# HuckyV2.net
KiCad netlist of a schematic drawn in EAGLE
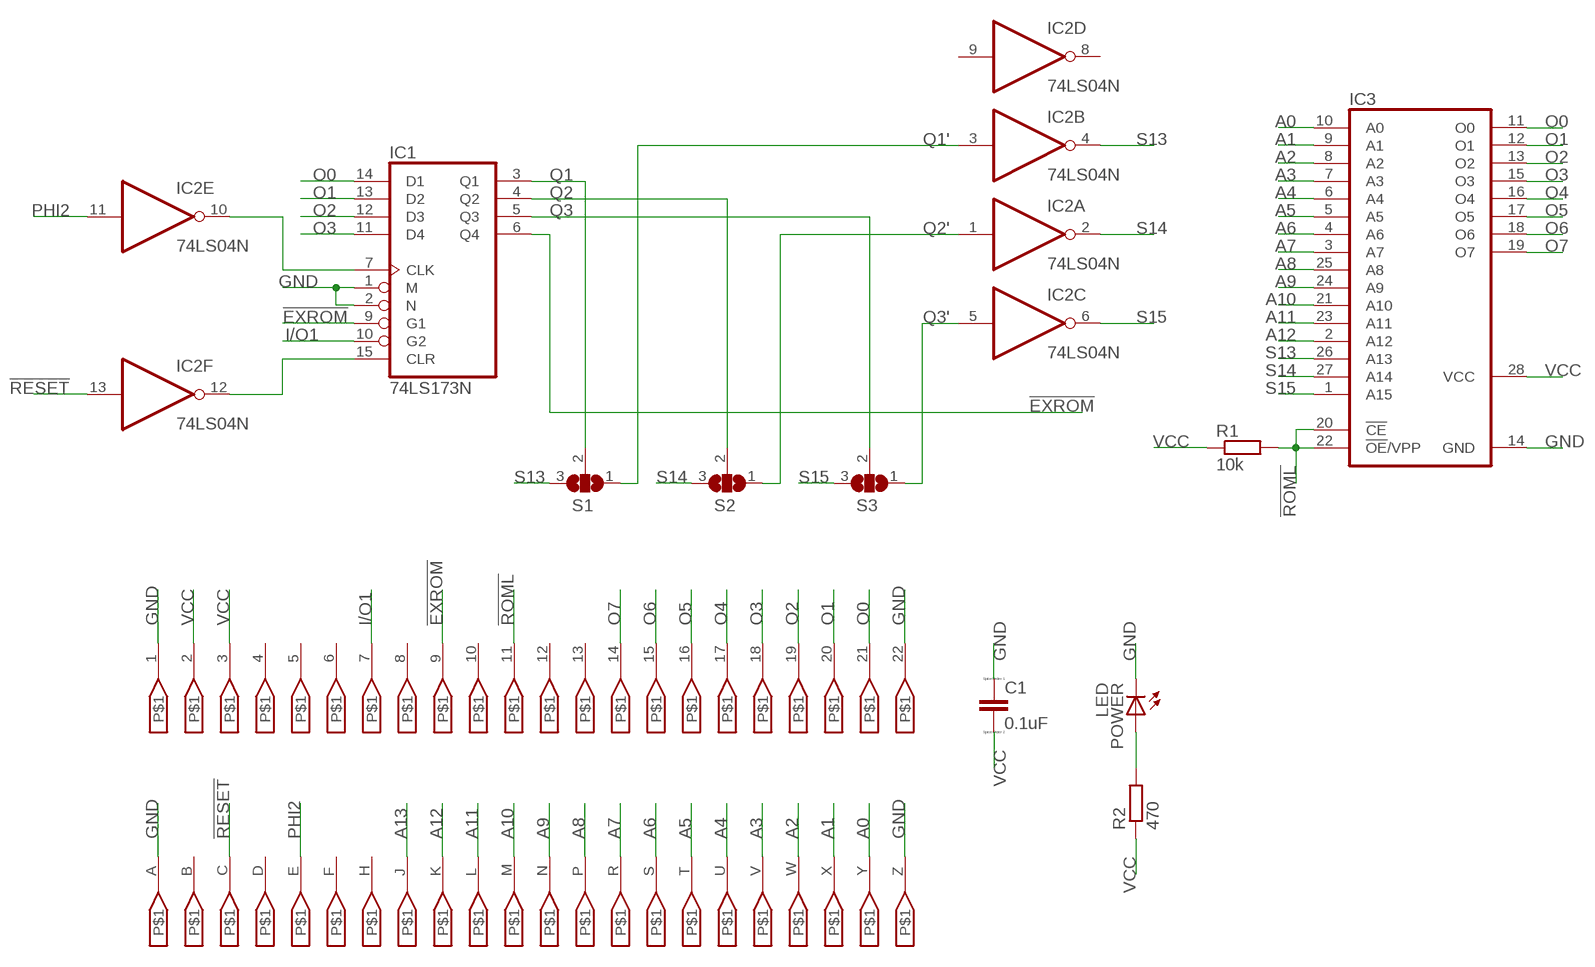
[diagram p0: schematic, sheet 1]

(export (version "E")
  (design (tool "Eeschema 10.0.6"))
  (components
    (comp (ref "C1")
      (value "0.1uF")
      (footprint "eagle-import:C050-24X044_SP")
      (libsource (lib "eagle-import") (part "C-EU050-24X044_SP"))
    )
    (comp (ref "IC1")
      (value "74LS173N")
      (footprint "eagle-import:DIL16")
      (libsource (lib "eagle-import") (part "74173NLS"))
    )
    (comp (ref "IC2")
      (value "74LS04N")
      (footprint "eagle-import:DIL14")
      (libsource (lib "eagle-import") (part "7404NLS"))
    )
    (comp (ref "IC3")
      (value "27C512D")
      (footprint "eagle-import:DIL28-6")
      (fields (field (name "MPN") "M27C512-10F1"))
      (libsource (lib "eagle-import") (part "27C512D"))
    )
    (comp (ref "POWER")
      (value "LED")
      (footprint "eagle-import:LED3MM_SMALLER_DRILL")
      (libsource (lib "eagle-import") (part "TLLG4400_SD"))
    )
    (comp (ref "R1")
      (value "10k")
      (footprint "eagle-import:0207_10_SP")
      (libsource (lib "eagle-import") (part "R-EU_0207/10_SP"))
    )
    (comp (ref "R2")
      (value "470")
      (footprint "eagle-import:0207_10_SP")
      (libsource (lib "eagle-import") (part "R-EU_0207/10_SP"))
    )
    (comp (ref "S1")
      (value "SJ2W_NUMBERED")
      (footprint "eagle-import:SJ_2_NUM")
      (libsource (lib "eagle-import") (part "SJ2W_NUMBERED"))
    )
    (comp (ref "S2")
      (value "SJ2W_NUMBERED")
      (footprint "eagle-import:SJ_2_NUM")
      (libsource (lib "eagle-import") (part "SJ2W_NUMBERED"))
    )
    (comp (ref "S3")
      (value "SJ2W_NUMBERED")
      (footprint "eagle-import:SJ_2_NUM")
      (libsource (lib "eagle-import") (part "SJ2W_NUMBERED"))
    )
    (comp (ref "U$1")
      (value "C64_EXPANSION_FINGERS_PIN8X1.9")
      (footprint "eagle-import:C64_EXPANSION_FINGERS_THINNER")
      (libsource (lib "eagle-import") (part "C64_EXPANSION_FINGERS_PIN8X1.9"))
    )
  )
  (nets
    (net (code "1") (name "/A0") (class "Default")
      (node (ref "IC3") (pin "10") (pinfunction "A0_10") (pintype "input"))
      (node (ref "U$1") (pin "Y") (pinfunction "P$1_Y") (pintype "bidirectional"))
    )
    (net (code "2") (name "/A1") (class "Default")
      (node (ref "IC3") (pin "9") (pinfunction "A1_9") (pintype "input"))
      (node (ref "U$1") (pin "X") (pinfunction "P$1_X") (pintype "bidirectional"))
    )
    (net (code "3") (name "/A2") (class "Default")
      (node (ref "IC3") (pin "8") (pinfunction "A2_8") (pintype "input"))
      (node (ref "U$1") (pin "W") (pinfunction "P$1_W") (pintype "bidirectional"))
    )
    (net (code "4") (name "/A3") (class "Default")
      (node (ref "IC3") (pin "7") (pinfunction "A3_7") (pintype "input"))
      (node (ref "U$1") (pin "V") (pinfunction "P$1_V") (pintype "bidirectional"))
    )
    (net (code "5") (name "/A4") (class "Default")
      (node (ref "IC3") (pin "6") (pinfunction "A4_6") (pintype "input"))
      (node (ref "U$1") (pin "U") (pinfunction "P$1_U") (pintype "bidirectional"))
    )
    (net (code "6") (name "/A5") (class "Default")
      (node (ref "IC3") (pin "5") (pinfunction "A5_5") (pintype "input"))
      (node (ref "U$1") (pin "T") (pinfunction "P$1_T") (pintype "bidirectional"))
    )
    (net (code "7") (name "/A6") (class "Default")
      (node (ref "IC3") (pin "4") (pinfunction "A6_4") (pintype "input"))
      (node (ref "U$1") (pin "S") (pinfunction "P$1_S") (pintype "bidirectional"))
    )
    (net (code "8") (name "/A7") (class "Default")
      (node (ref "IC3") (pin "3") (pinfunction "A7_3") (pintype "input"))
      (node (ref "U$1") (pin "R") (pinfunction "P$1_R") (pintype "bidirectional"))
    )
    (net (code "9") (name "/A8") (class "Default")
      (node (ref "IC3") (pin "25") (pinfunction "A8_25") (pintype "input"))
      (node (ref "U$1") (pin "P") (pinfunction "P$1_P") (pintype "bidirectional"))
    )
    (net (code "10") (name "/A9") (class "Default")
      (node (ref "IC3") (pin "24") (pinfunction "A9_24") (pintype "input"))
      (node (ref "U$1") (pin "N") (pinfunction "P$1_N") (pintype "bidirectional"))
    )
    (net (code "11") (name "/A10") (class "Default")
      (node (ref "IC3") (pin "21") (pinfunction "A10_21") (pintype "input"))
      (node (ref "U$1") (pin "M") (pinfunction "P$1_M") (pintype "bidirectional"))
    )
    (net (code "12") (name "/A11") (class "Default")
      (node (ref "IC3") (pin "23") (pinfunction "A11_23") (pintype "input"))
      (node (ref "U$1") (pin "L") (pinfunction "P$1_L") (pintype "bidirectional"))
    )
    (net (code "13") (name "/A12") (class "Default")
      (node (ref "IC3") (pin "2") (pinfunction "A12_2") (pintype "input"))
      (node (ref "U$1") (pin "K") (pinfunction "P$1_K") (pintype "bidirectional"))
    )
    (net (code "14") (name "/A13") (class "Default")
      (node (ref "U$1") (pin "J") (pinfunction "P$1_J") (pintype "bidirectional"))
    )
    (net (code "15") (name "/GND") (class "Default")
      (node (ref "C1") (pin "1") (pinfunction "1_1") (pintype "passive"))
      (node (ref "IC1") (pin "1") (pinfunction "M_1") (pintype "input"))
      (node (ref "IC1") (pin "2") (pinfunction "N_2") (pintype "input"))
      (node (ref "IC3") (pin "14") (pinfunction "GND_14") (pintype "power_in"))
      (node (ref "POWER") (pin "K") (pinfunction "C_K") (pintype "passive"))
      (node (ref "U$1") (pin "1") (pinfunction "P$1_1") (pintype "bidirectional"))
      (node (ref "U$1") (pin "22") (pinfunction "P$1_22") (pintype "bidirectional"))
      (node (ref "U$1") (pin "A") (pinfunction "P$1_A") (pintype "bidirectional"))
      (node (ref "U$1") (pin "Z") (pinfunction "P$1_Z") (pintype "bidirectional"))
    )
    (net (code "16") (name "/I{slash}O1") (class "Default")
      (node (ref "IC1") (pin "10") (pinfunction "G2_10") (pintype "input"))
      (node (ref "U$1") (pin "7") (pinfunction "P$1_7") (pintype "bidirectional"))
    )
    (net (code "17") (name "/O0") (class "Default")
      (node (ref "IC1") (pin "14") (pinfunction "D1_14") (pintype "input"))
      (node (ref "IC3") (pin "11") (pinfunction "O0_11") (pintype "tri_state"))
      (node (ref "U$1") (pin "21") (pinfunction "P$1_21") (pintype "bidirectional"))
    )
    (net (code "18") (name "/O1") (class "Default")
      (node (ref "IC1") (pin "13") (pinfunction "D2_13") (pintype "input"))
      (node (ref "IC3") (pin "12") (pinfunction "O1_12") (pintype "tri_state"))
      (node (ref "U$1") (pin "20") (pinfunction "P$1_20") (pintype "bidirectional"))
    )
    (net (code "19") (name "/O2") (class "Default")
      (node (ref "IC1") (pin "12") (pinfunction "D3_12") (pintype "input"))
      (node (ref "IC3") (pin "13") (pinfunction "O2_13") (pintype "tri_state"))
      (node (ref "U$1") (pin "19") (pinfunction "P$1_19") (pintype "bidirectional"))
    )
    (net (code "20") (name "/O3") (class "Default")
      (node (ref "IC1") (pin "11") (pinfunction "D4_11") (pintype "input"))
      (node (ref "IC3") (pin "15") (pinfunction "O3_15") (pintype "tri_state"))
      (node (ref "U$1") (pin "18") (pinfunction "P$1_18") (pintype "bidirectional"))
    )
    (net (code "21") (name "/O4") (class "Default")
      (node (ref "IC3") (pin "16") (pinfunction "O4_16") (pintype "tri_state"))
      (node (ref "U$1") (pin "17") (pinfunction "P$1_17") (pintype "bidirectional"))
    )
    (net (code "22") (name "/O5") (class "Default")
      (node (ref "IC3") (pin "17") (pinfunction "O5_17") (pintype "tri_state"))
      (node (ref "U$1") (pin "16") (pinfunction "P$1_16") (pintype "bidirectional"))
    )
    (net (code "23") (name "/O6") (class "Default")
      (node (ref "IC3") (pin "18") (pinfunction "O6_18") (pintype "tri_state"))
      (node (ref "U$1") (pin "15") (pinfunction "P$1_15") (pintype "bidirectional"))
    )
    (net (code "24") (name "/O7") (class "Default")
      (node (ref "IC3") (pin "19") (pinfunction "O7_19") (pintype "tri_state"))
      (node (ref "U$1") (pin "14") (pinfunction "P$1_14") (pintype "bidirectional"))
    )
    (net (code "25") (name "/PHI2") (class "Default")
      (node (ref "IC2") (pin "11") (pinfunction "I_11") (pintype "input"))
      (node (ref "U$1") (pin "E") (pinfunction "P$1_E") (pintype "bidirectional"))
    )
    (net (code "26") (name "/Q1") (class "Default")
      (node (ref "IC1") (pin "3") (pinfunction "Q1_3") (pintype "tri_state"))
      (node (ref "S1") (pin "2") (pinfunction "2_2") (pintype "passive"))
    )
    (net (code "27") (name "/Q1'") (class "Default")
      (node (ref "IC2") (pin "3") (pinfunction "I_3") (pintype "input"))
      (node (ref "S1") (pin "1") (pinfunction "1_1") (pintype "passive"))
    )
    (net (code "28") (name "/Q2") (class "Default")
      (node (ref "IC1") (pin "4") (pinfunction "Q2_4") (pintype "tri_state"))
      (node (ref "S2") (pin "2") (pinfunction "2_2") (pintype "passive"))
    )
    (net (code "29") (name "/Q2'") (class "Default")
      (node (ref "IC2") (pin "1") (pinfunction "I_1") (pintype "input"))
      (node (ref "S2") (pin "1") (pinfunction "1_1") (pintype "passive"))
    )
    (net (code "30") (name "/Q3") (class "Default")
      (node (ref "IC1") (pin "5") (pinfunction "Q3_5") (pintype "tri_state"))
      (node (ref "S3") (pin "2") (pinfunction "2_2") (pintype "passive"))
    )
    (net (code "31") (name "/Q3'") (class "Default")
      (node (ref "IC2") (pin "5") (pinfunction "I_5") (pintype "input"))
      (node (ref "S3") (pin "1") (pinfunction "1_1") (pintype "passive"))
    )
    (net (code "32") (name "/S13") (class "Default")
      (node (ref "IC2") (pin "4") (pinfunction "O_4") (pintype "output"))
      (node (ref "IC3") (pin "26") (pinfunction "A13_26") (pintype "input"))
      (node (ref "S1") (pin "3") (pinfunction "3_3") (pintype "passive"))
    )
    (net (code "33") (name "/S14") (class "Default")
      (node (ref "IC2") (pin "2") (pinfunction "O_2") (pintype "output"))
      (node (ref "IC3") (pin "27") (pinfunction "A14_27") (pintype "input"))
      (node (ref "S2") (pin "3") (pinfunction "3_3") (pintype "passive"))
    )
    (net (code "34") (name "/S15") (class "Default")
      (node (ref "IC2") (pin "6") (pinfunction "O_6") (pintype "output"))
      (node (ref "IC3") (pin "1") (pinfunction "A15_1") (pintype "input"))
      (node (ref "S3") (pin "3") (pinfunction "3_3") (pintype "passive"))
    )
    (net (code "35") (name "/VCC") (class "Default")
      (node (ref "C1") (pin "2") (pinfunction "2_2") (pintype "passive"))
      (node (ref "IC3") (pin "28") (pinfunction "VCC_28") (pintype "power_in"))
      (node (ref "R1") (pin "1") (pinfunction "1_1") (pintype "passive"))
      (node (ref "R2") (pin "1") (pinfunction "1_1") (pintype "passive"))
      (node (ref "U$1") (pin "2") (pinfunction "P$1_2") (pintype "bidirectional"))
      (node (ref "U$1") (pin "3") (pinfunction "P$1_3") (pintype "bidirectional"))
    )
    (net (code "36") (name "/~{EXROM}") (class "Default")
      (node (ref "IC1") (pin "6") (pinfunction "Q4_6") (pintype "tri_state"))
      (node (ref "IC1") (pin "9") (pinfunction "G1_9") (pintype "input"))
      (node (ref "U$1") (pin "9") (pinfunction "P$1_9") (pintype "bidirectional"))
    )
    (net (code "37") (name "/~{RESET}") (class "Default")
      (node (ref "IC2") (pin "13") (pinfunction "I_13") (pintype "input"))
      (node (ref "U$1") (pin "C") (pinfunction "P$1_C") (pintype "bidirectional"))
    )
    (net (code "38") (name "/~{ROML}") (class "Default")
      (node (ref "IC3") (pin "20") (pinfunction "~{CE}_20") (pintype "input"))
      (node (ref "IC3") (pin "22") (pinfunction "~{OE}/VPP_22") (pintype "input"))
      (node (ref "R1") (pin "2") (pinfunction "2_2") (pintype "passive"))
      (node (ref "U$1") (pin "11") (pinfunction "P$1_11") (pintype "bidirectional"))
    )
    (net (code "39") (name "Net-(IC1A-CLK)") (class "Default")
      (node (ref "IC1") (pin "7") (pinfunction "CLK_7") (pintype "input"))
      (node (ref "IC2") (pin "10") (pinfunction "O_10") (pintype "output"))
    )
    (net (code "40") (name "Net-(IC1A-CLR)") (class "Default")
      (node (ref "IC1") (pin "15") (pinfunction "CLR_15") (pintype "input"))
      (node (ref "IC2") (pin "12") (pinfunction "O_12") (pintype "output"))
    )
    (net (code "41") (name "Net-(POWER-PadA)") (class "Default")
      (node (ref "POWER") (pin "A") (pinfunction "A_A") (pintype "passive"))
      (node (ref "R2") (pin "2") (pinfunction "2_2") (pintype "passive"))
    )
    (net (code "42") (name "unconnected-(IC2D-I-Pad9)") (class "Default")
      (node (ref "IC2") (pin "9") (pinfunction "I_9") (pintype "input"))
    )
    (net (code "43") (name "unconnected-(IC2D-O-Pad8)") (class "Default")
      (node (ref "IC2") (pin "8") (pinfunction "O_8") (pintype "output"))
    )
    (net (code "44") (name "unconnected-(U$1AH-P$1-Pad4)") (class "Default")
      (node (ref "U$1") (pin "4") (pinfunction "P$1_4") (pintype "bidirectional"))
    )
    (net (code "45") (name "unconnected-(U$1AN-P$1-Pad5)") (class "Default")
      (node (ref "U$1") (pin "5") (pinfunction "P$1_5") (pintype "bidirectional"))
    )
    (net (code "46") (name "unconnected-(U$1AO-P$1-Pad6)") (class "Default")
      (node (ref "U$1") (pin "6") (pinfunction "P$1_6") (pintype "bidirectional"))
    )
    (net (code "47") (name "unconnected-(U$1AQ-P$1-Pad8)") (class "Default")
      (node (ref "U$1") (pin "8") (pinfunction "P$1_8") (pintype "bidirectional"))
    )
    (net (code "48") (name "unconnected-(U$1B-P$1-Pad10)") (class "Default")
      (node (ref "U$1") (pin "10") (pinfunction "P$1_10") (pintype "bidirectional"))
    )
    (net (code "49") (name "unconnected-(U$1D-P$1-Pad12)") (class "Default")
      (node (ref "U$1") (pin "12") (pinfunction "P$1_12") (pintype "bidirectional"))
    )
    (net (code "50") (name "unconnected-(U$1E-P$1-Pad13)") (class "Default")
      (node (ref "U$1") (pin "13") (pinfunction "P$1_13") (pintype "bidirectional"))
    )
    (net (code "51") (name "unconnected-(U$1Q-P$1-PadB)") (class "Default")
      (node (ref "U$1") (pin "B") (pinfunction "P$1_B") (pintype "bidirectional"))
    )
    (net (code "52") (name "unconnected-(U$1S-P$1-PadD)") (class "Default")
      (node (ref "U$1") (pin "D") (pinfunction "P$1_D") (pintype "bidirectional"))
    )
    (net (code "53") (name "unconnected-(U$1U-P$1-PadF)") (class "Default")
      (node (ref "U$1") (pin "F") (pinfunction "P$1_F") (pintype "bidirectional"))
    )
    (net (code "54") (name "unconnected-(U$1V-P$1-PadH)") (class "Default")
      (node (ref "U$1") (pin "H") (pinfunction "P$1_H") (pintype "bidirectional"))
    )
  )
)
